# EuroDrum.net
KiCad netlist of a schematic drawn in EAGLE
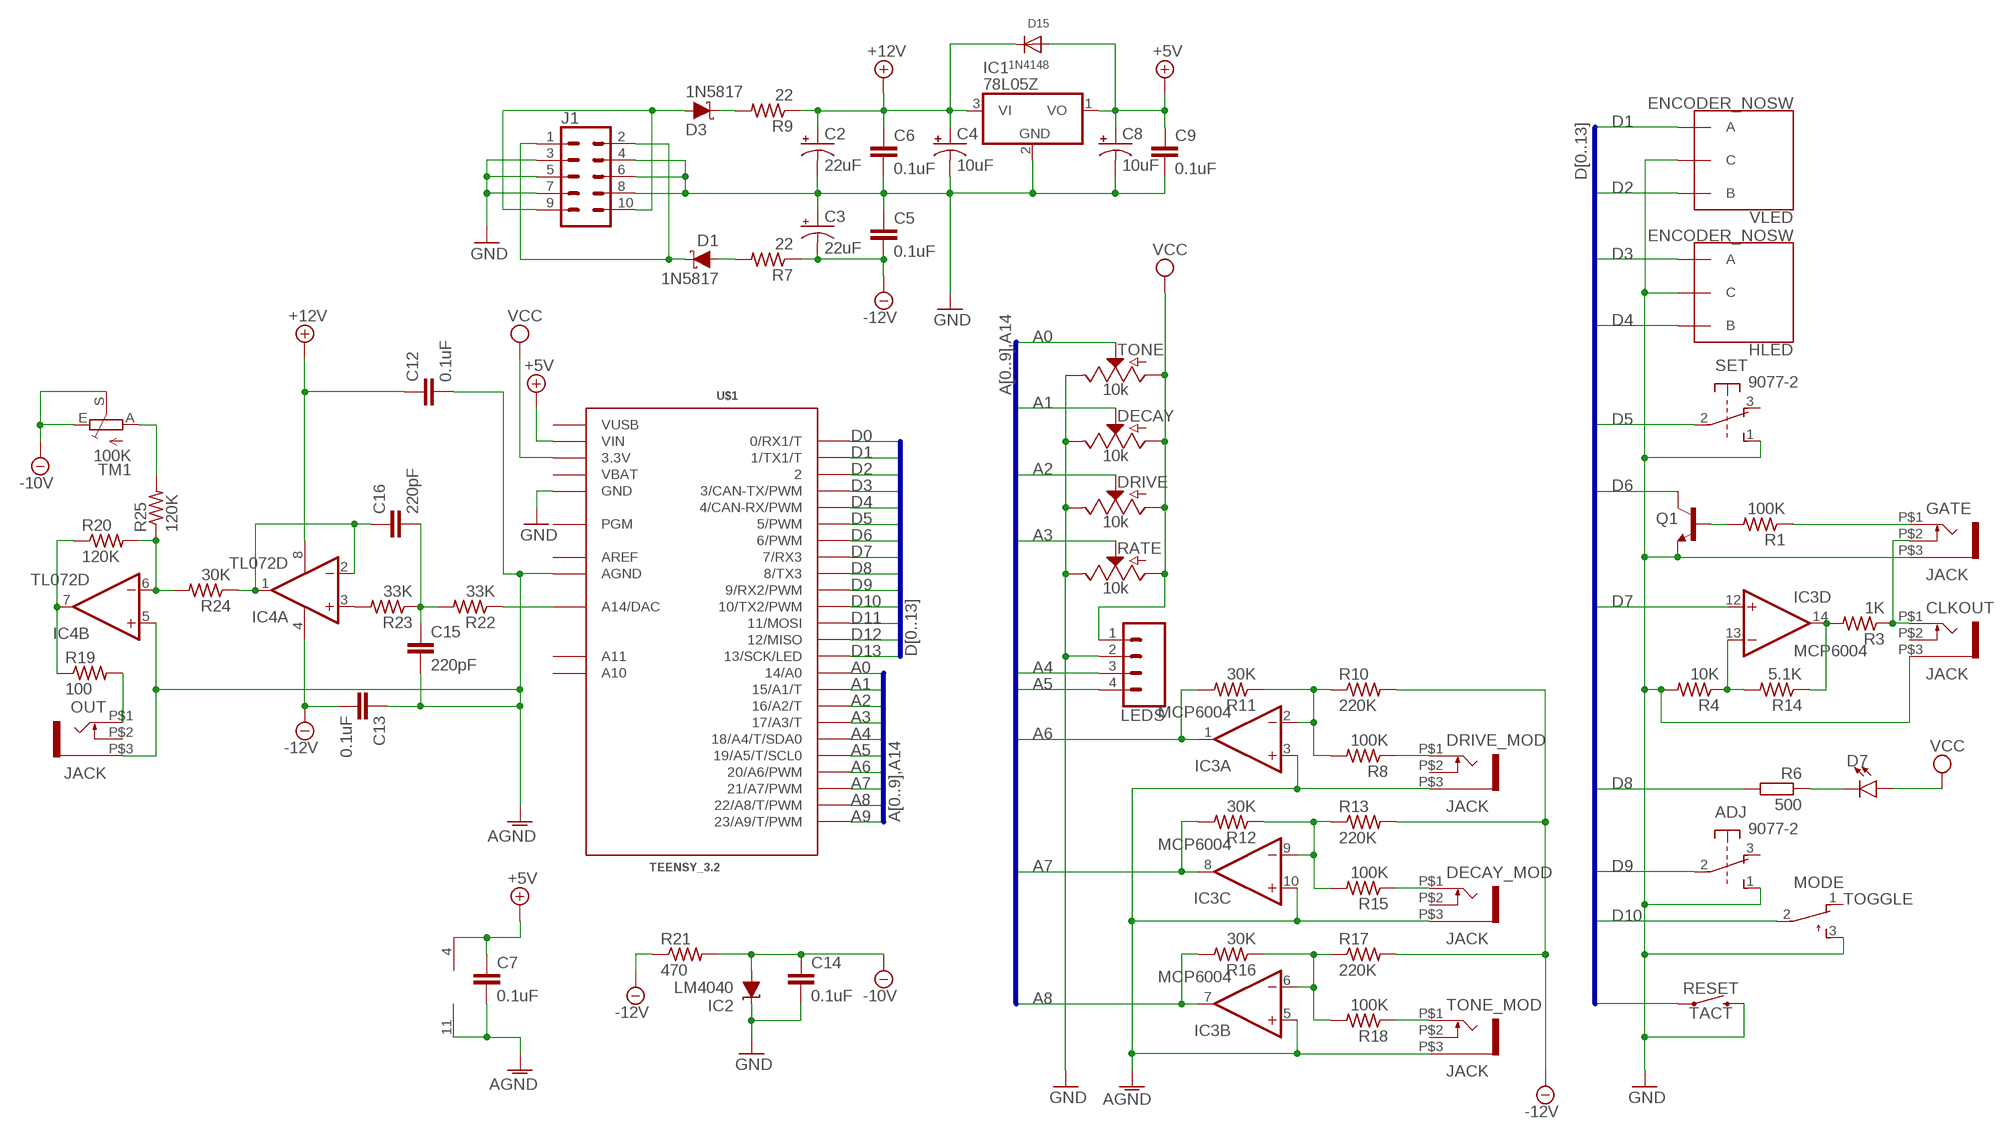
[diagram p0: schematic, sheet 1]

(export (version "E")
  (design (tool "Eeschema 10.0.6"))
  (components
    (comp (ref "ADJ")
      (value "9077-2")
      (footprint "eagle-import:9077-2")
      (libsource (lib "eagle-import") (part "9077-2"))
    )
    (comp (ref "C2")
      (value "22uF")
      (footprint "eagle-import:CPOL-RADIAL-2.5MM-5MM")
      (libsource (lib "eagle-import") (part "10UF-POLAR-RADIAL-2.5MM-25V-20%"))
    )
    (comp (ref "C3")
      (value "22uF")
      (footprint "eagle-import:CPOL-RADIAL-2.5MM-5MM")
      (libsource (lib "eagle-import") (part "10UF-POLAR-RADIAL-2.5MM-25V-20%"))
    )
    (comp (ref "C4")
      (value "10uF")
      (footprint "eagle-import:CPOL-RADIAL-2.5MM-5MM")
      (libsource (lib "eagle-import") (part "10UF-POLAR-RADIAL-2.5MM-25V-20%"))
    )
    (comp (ref "C5")
      (value "0.1uF")
      (footprint "eagle-import:C0603K")
      (libsource (lib "eagle-import") (part "C-EUC0603K"))
    )
    (comp (ref "C6")
      (value "0.1uF")
      (footprint "eagle-import:C0603K")
      (libsource (lib "eagle-import") (part "C-EUC0603K"))
    )
    (comp (ref "C7")
      (value "0.1uF")
      (footprint "eagle-import:C0603K")
      (libsource (lib "eagle-import") (part "C-EUC0603K"))
    )
    (comp (ref "C8")
      (value "10uF")
      (footprint "eagle-import:CPOL-RADIAL-2.5MM-5MM")
      (libsource (lib "eagle-import") (part "10UF-POLAR-RADIAL-2.5MM-25V-20%"))
    )
    (comp (ref "C9")
      (value "0.1uF")
      (footprint "eagle-import:C0603K")
      (libsource (lib "eagle-import") (part "C-EUC0603K"))
    )
    (comp (ref "C12")
      (value "0.1uF")
      (footprint "eagle-import:C0603K")
      (libsource (lib "eagle-import") (part "C-EUC0603K"))
    )
    (comp (ref "C13")
      (value "0.1uF")
      (footprint "eagle-import:C0603K")
      (libsource (lib "eagle-import") (part "C-EUC0603K"))
    )
    (comp (ref "C14")
      (value "0.1uF")
      (footprint "eagle-import:C0603K")
      (libsource (lib "eagle-import") (part "C-EUC0603K"))
    )
    (comp (ref "C15")
      (value "220pF")
      (footprint "eagle-import:C0603K")
      (libsource (lib "eagle-import") (part "C-EUC0603K"))
    )
    (comp (ref "C16")
      (value "220pF")
      (footprint "eagle-import:C0603K")
      (libsource (lib "eagle-import") (part "C-EUC0603K"))
    )
    (comp (ref "CLKOUT")
      (value "JACK")
      (footprint "eagle-import:WQP-PJ301M-12_JACK")
      (libsource (lib "eagle-import") (part "WQP-PJ301M-12_JACK"))
    )
    (comp (ref "D1")
      (value "1N5817")
      (footprint "eagle-import:SOD-323")
      (libsource (lib "eagle-import") (part "DIODE-SCHOTTKY-BAT60A"))
    )
    (comp (ref "D3")
      (value "1N5817")
      (footprint "eagle-import:SOD-323")
      (libsource (lib "eagle-import") (part "DIODE-SCHOTTKY-BAT60A"))
    )
    (comp (ref "D7")
      (value "LED3MM")
      (footprint "eagle-import:LED_3MM")
      (fields (field (name "PROD_ID") "DIO-08794"))
      (libsource (lib "eagle-import") (part "LED3MM"))
    )
    (comp (ref "D15")
      (value "1N4148")
      (footprint "eagle-import:SOD-123")
      (libsource (lib "eagle-import") (part "DIODESOD-123"))
    )
    (comp (ref "DECAY")
      (value "10k")
      (footprint "eagle-import:POT-PTH-ALPS")
      (libsource (lib "eagle-import") (part "POTENTIOMETER-PTH-9MM-1/20W-20%"))
    )
    (comp (ref "DECAY_MOD")
      (value "JACK")
      (footprint "eagle-import:WQP-PJ301M-12_JACK")
      (libsource (lib "eagle-import") (part "WQP-PJ301M-12_JACK"))
    )
    (comp (ref "DRIVE")
      (value "10k")
      (footprint "eagle-import:POT-PTH-ALPS")
      (libsource (lib "eagle-import") (part "POTENTIOMETER-PTH-9MM-1/20W-20%"))
    )
    (comp (ref "DRIVE_MOD")
      (value "JACK")
      (footprint "eagle-import:WQP-PJ301M-12_JACK")
      (libsource (lib "eagle-import") (part "WQP-PJ301M-12_JACK"))
    )
    (comp (ref "GATE")
      (value "JACK")
      (footprint "eagle-import:WQP-PJ301M-12_JACK")
      (libsource (lib "eagle-import") (part "WQP-PJ301M-12_JACK"))
    )
    (comp (ref "HLED")
      (value "ENCODER_NOSW")
      (footprint "eagle-import:ENCODER_NOSW")
      (libsource (lib "eagle-import") (part "ENCODER_NOSW"))
    )
    (comp (ref "IC1")
      (value "78L05Z")
      (footprint "eagle-import:TO92")
      (libsource (lib "eagle-import") (part "78ZL05"))
    )
    (comp (ref "IC2")
      (value "LM4040")
      (footprint "eagle-import:DBZ_R-PDSO-G3")
      (fields (field (name "MPN") "LM4041A12IDBZR"))
      (libsource (lib "eagle-import") (part "LM4041DBZA12"))
    )
    (comp (ref "IC3")
      (value "MCP6004")
      (footprint "eagle-import:SO14")
      (libsource (lib "eagle-import") (part "4AMP_P4+11D"))
    )
    (comp (ref "IC4")
      (value "TL072D")
      (footprint "eagle-import:SO08")
      (libsource (lib "eagle-import") (part "TL072D"))
    )
    (comp (ref "J1")
      (value "CONN_05X2SHD")
      (footprint "eagle-import:2X5-SHROUDED")
      (libsource (lib "eagle-import") (part "CONN_05X2SHD"))
    )
    (comp (ref "LEDS")
      (value "CONN_04LONGPADS")
      (footprint "eagle-import:1X04_LONGPADS")
      (libsource (lib "eagle-import") (part "CONN_04LONGPADS"))
    )
    (comp (ref "MODE")
      (value "TOGGLE")
      (footprint "eagle-import:TL3XYO")
      (libsource (lib "eagle-import") (part "TL32YOSP_BKT"))
    )
    (comp (ref "OUT")
      (value "JACK")
      (footprint "eagle-import:WQP-PJ301M-12_JACK")
      (libsource (lib "eagle-import") (part "WQP-PJ301M-12_JACK"))
    )
    (comp (ref "Q1")
      (value "BC549C")
      (footprint "eagle-import:TO92-EBC")
      (libsource (lib "eagle-import") (part "BC549C"))
    )
    (comp (ref "R1")
      (value "100K")
      (footprint "eagle-import:R0603")
      (libsource (lib "eagle-import") (part "rcl_334_R-US_R0603"))
    )
    (comp (ref "R3")
      (value "1K")
      (footprint "eagle-import:R0603")
      (libsource (lib "eagle-import") (part "rcl_334_R-US_R0603"))
    )
    (comp (ref "R4")
      (value "10K")
      (footprint "eagle-import:R0603")
      (libsource (lib "eagle-import") (part "R-US_R0603"))
    )
    (comp (ref "R6")
      (value "500")
      (footprint "eagle-import:R0603")
      (libsource (lib "eagle-import") (part "R-EU_R0603"))
    )
    (comp (ref "R7")
      (value "22")
      (footprint "eagle-import:R0603")
      (libsource (lib "eagle-import") (part "rcl_334_R-US_R0603"))
    )
    (comp (ref "R8")
      (value "100K")
      (footprint "eagle-import:R0603")
      (libsource (lib "eagle-import") (part "rcl_334_R-US_R0603"))
    )
    (comp (ref "R9")
      (value "22")
      (footprint "eagle-import:R0603")
      (libsource (lib "eagle-import") (part "rcl_334_R-US_R0603"))
    )
    (comp (ref "R10")
      (value "220K")
      (footprint "eagle-import:R0603")
      (libsource (lib "eagle-import") (part "rcl_334_R-US_R0603"))
    )
    (comp (ref "R11")
      (value "30K")
      (footprint "eagle-import:R0603")
      (libsource (lib "eagle-import") (part "rcl_334_R-US_R0603"))
    )
    (comp (ref "R12")
      (value "30K")
      (footprint "eagle-import:R0603")
      (libsource (lib "eagle-import") (part "rcl_334_R-US_R0603"))
    )
    (comp (ref "R13")
      (value "220K")
      (footprint "eagle-import:R0603")
      (libsource (lib "eagle-import") (part "rcl_334_R-US_R0603"))
    )
    (comp (ref "R14")
      (value "5.1K")
      (footprint "eagle-import:R0603")
      (libsource (lib "eagle-import") (part "R-US_R0603"))
    )
    (comp (ref "R15")
      (value "100K")
      (footprint "eagle-import:R0603")
      (libsource (lib "eagle-import") (part "rcl_334_R-US_R0603"))
    )
    (comp (ref "R16")
      (value "30K")
      (footprint "eagle-import:R0603")
      (libsource (lib "eagle-import") (part "rcl_334_R-US_R0603"))
    )
    (comp (ref "R17")
      (value "220K")
      (footprint "eagle-import:R0603")
      (libsource (lib "eagle-import") (part "rcl_334_R-US_R0603"))
    )
    (comp (ref "R18")
      (value "100K")
      (footprint "eagle-import:R0603")
      (libsource (lib "eagle-import") (part "rcl_334_R-US_R0603"))
    )
    (comp (ref "R19")
      (value "100")
      (footprint "eagle-import:R0603")
      (libsource (lib "eagle-import") (part "rcl_334_R-US_R0603"))
    )
    (comp (ref "R20")
      (value "120K")
      (footprint "eagle-import:R0603")
      (libsource (lib "eagle-import") (part "rcl_334_R-US_R0603"))
    )
    (comp (ref "R21")
      (value "470")
      (footprint "eagle-import:R0603")
      (libsource (lib "eagle-import") (part "rcl_334_R-US_R0603"))
    )
    (comp (ref "R22")
      (value "33K")
      (footprint "eagle-import:R0603")
      (libsource (lib "eagle-import") (part "rcl_334_R-US_R0603"))
    )
    (comp (ref "R23")
      (value "33K")
      (footprint "eagle-import:R0603")
      (libsource (lib "eagle-import") (part "rcl_334_R-US_R0603"))
    )
    (comp (ref "R24")
      (value "30K")
      (footprint "eagle-import:R0603")
      (libsource (lib "eagle-import") (part "rcl_334_R-US_R0603"))
    )
    (comp (ref "R25")
      (value "120K")
      (footprint "eagle-import:R0603")
      (libsource (lib "eagle-import") (part "rcl_334_R-US_R0603"))
    )
    (comp (ref "RATE")
      (value "10k")
      (footprint "eagle-import:POT-PTH-ALPS")
      (libsource (lib "eagle-import") (part "POTENTIOMETER-PTH-9MM-1/20W-20%"))
    )
    (comp (ref "RESET")
      (value "TACT")
      (footprint "eagle-import:TACTILE_SWITCH_PTH_6.0MM")
      (libsource (lib "eagle-import") (part "MOMENTARY-SWITCH-SPST-PTH-6.0MM"))
    )
    (comp (ref "SET")
      (value "9077-2")
      (footprint "eagle-import:9077-2")
      (libsource (lib "eagle-import") (part "9077-2"))
    )
    (comp (ref "TM1")
      (value "100K")
      (footprint "eagle-import:CA6H")
      (libsource (lib "eagle-import") (part "TRIM_EU-CA6H"))
    )
    (comp (ref "TONE")
      (value "10k")
      (footprint "eagle-import:POT-PTH-ALPS")
      (libsource (lib "eagle-import") (part "POTENTIOMETER-PTH-9MM-1/20W-20%"))
    )
    (comp (ref "TONE_MOD")
      (value "JACK")
      (footprint "eagle-import:WQP-PJ301M-12_JACK")
      (libsource (lib "eagle-import") (part "WQP-PJ301M-12_JACK"))
    )
    (comp (ref "U$1")
      (value "TEENSY_3.2")
      (footprint "eagle-import:TEENSY_3.0-3.2&LC_ALL_PINS")
      (libsource (lib "eagle-import") (part "TEENSY_3.1-3.2_ALL_PINS"))
    )
    (comp (ref "VLED")
      (value "ENCODER_NOSW")
      (footprint "eagle-import:ENCODER_NOSW")
      (libsource (lib "eagle-import") (part "ENCODER_NOSW"))
    )
  )
  (nets
    (net (code "2") (name "+5V") (class "Default")
      (node (ref "C7") (pin "1") (pinfunction "1_1") (pintype "passive"))
      (node (ref "C8") (pin "1") (pinfunction "+_1") (pintype "passive"))
      (node (ref "C9") (pin "1") (pinfunction "1_1") (pintype "passive"))
      (node (ref "D15") (pin "A") (pinfunction "A_A") (pintype "passive"))
      (node (ref "IC1") (pin "1") (pinfunction "VO_1") (pintype "passive"))
      (node (ref "IC3") (pin "4") (pinfunction "V+_4") (pintype "power_in"))
      (node (ref "U$1") (pin "VIN") (pinfunction "VIN_VIN") (pintype "power_in"))
    )
    (net (code "3") (name "+12V") (class "Default")
      (node (ref "C12") (pin "1") (pinfunction "1_1") (pintype "passive"))
      (node (ref "C2") (pin "1") (pinfunction "+_1") (pintype "passive"))
      (node (ref "C4") (pin "1") (pinfunction "+_1") (pintype "passive"))
      (node (ref "C6") (pin "1") (pinfunction "1_1") (pintype "passive"))
      (node (ref "D15") (pin "C") (pinfunction "C_C") (pintype "passive"))
      (node (ref "IC1") (pin "3") (pinfunction "VI_3") (pintype "input"))
      (node (ref "IC4") (pin "8") (pinfunction "V+_8") (pintype "power_in"))
      (node (ref "R9") (pin "1") (pinfunction "1_1") (pintype "passive"))
    )
    (net (code "4") (name "-10V") (class "Default")
      (node (ref "C14") (pin "1") (pinfunction "1_1") (pintype "passive"))
      (node (ref "IC2") (pin "2") (pinfunction "A_2") (pintype "passive"))
      (node (ref "R21") (pin "2") (pinfunction "2_2") (pintype "passive"))
      (node (ref "TM1") (pin "E") (pinfunction "E_E") (pintype "passive"))
      (node (ref "TM1") (pin "S") (pinfunction "S_S") (pintype "passive"))
    )
    (net (code "5") (name "-12V") (class "Default")
      (node (ref "C13") (pin "2") (pinfunction "2_2") (pintype "passive"))
      (node (ref "C3") (pin "2") (pinfunction "-_2") (pintype "passive"))
      (node (ref "C5") (pin "2") (pinfunction "2_2") (pintype "passive"))
      (node (ref "IC4") (pin "4") (pinfunction "V-_4") (pintype "power_in"))
      (node (ref "R10") (pin "2") (pinfunction "2_2") (pintype "passive"))
      (node (ref "R13") (pin "2") (pinfunction "2_2") (pintype "passive"))
      (node (ref "R17") (pin "2") (pinfunction "2_2") (pintype "passive"))
      (node (ref "R21") (pin "1") (pinfunction "1_1") (pintype "passive"))
      (node (ref "R7") (pin "1") (pinfunction "1_1") (pintype "passive"))
    )
    (net (code "6") (name "/A0") (class "Default")
      (node (ref "TONE") (pin "P$2") (pinfunction "S_P$2") (pintype "passive"))
      (node (ref "U$1") (pin "14/A0") (pinfunction "14/A0_14/A0") (pintype "bidirectional"))
    )
    (net (code "7") (name "/A1") (class "Default")
      (node (ref "DECAY") (pin "P$2") (pinfunction "S_P$2") (pintype "passive"))
      (node (ref "U$1") (pin "15/A1") (pinfunction "15/A1/T_15/A1") (pintype "bidirectional"))
    )
    (net (code "8") (name "/A2") (class "Default")
      (node (ref "DRIVE") (pin "P$2") (pinfunction "S_P$2") (pintype "passive"))
      (node (ref "U$1") (pin "16/A2") (pinfunction "16/A2/T_16/A2") (pintype "bidirectional"))
    )
    (net (code "9") (name "/A3") (class "Default")
      (node (ref "RATE") (pin "P$2") (pinfunction "S_P$2") (pintype "passive"))
      (node (ref "U$1") (pin "17/A3") (pinfunction "17/A3/T_17/A3") (pintype "bidirectional"))
    )
    (net (code "10") (name "/A4") (class "Default")
      (node (ref "LEDS") (pin "3") (pinfunction "3_3") (pintype "passive"))
      (node (ref "U$1") (pin "18/A4") (pinfunction "18/A4/T/SDA0_18/A4") (pintype "bidirectional"))
    )
    (net (code "11") (name "/A5") (class "Default")
      (node (ref "LEDS") (pin "4") (pinfunction "4_4") (pintype "passive"))
      (node (ref "U$1") (pin "19/A5") (pinfunction "19/A5/T/SCL0_19/A5") (pintype "bidirectional"))
    )
    (net (code "12") (name "/A6") (class "Default")
      (node (ref "IC3") (pin "1") (pinfunction "OUT_1") (pintype "output"))
      (node (ref "R11") (pin "2") (pinfunction "2_2") (pintype "passive"))
      (node (ref "U$1") (pin "20/A6") (pinfunction "20/A6/PWM_20/A6") (pintype "bidirectional"))
    )
    (net (code "13") (name "/A7") (class "Default")
      (node (ref "IC3") (pin "8") (pinfunction "OUT_8") (pintype "output"))
      (node (ref "R12") (pin "2") (pinfunction "2_2") (pintype "passive"))
      (node (ref "U$1") (pin "21/A7") (pinfunction "21/A7/PWM_21/A7") (pintype "bidirectional"))
    )
    (net (code "14") (name "/A8") (class "Default")
      (node (ref "IC3") (pin "7") (pinfunction "OUT_7") (pintype "output"))
      (node (ref "R16") (pin "2") (pinfunction "2_2") (pintype "passive"))
      (node (ref "U$1") (pin "22/A8") (pinfunction "22/A8/T/PWM_22/A8") (pintype "bidirectional"))
    )
    (net (code "15") (name "/A9") (class "Default")
      (node (ref "U$1") (pin "23/A9") (pinfunction "23/A9/T/PWM_23/A9") (pintype "bidirectional"))
    )
    (net (code "16") (name "/AREF") (class "Default")
      (node (ref "U$1") (pin "AREF") (pinfunction "AREF_AREF") (pintype "power_in"))
    )
    (net (code "17") (name "/D0") (class "Default")
      (node (ref "U$1") (pin "0") (pinfunction "0/RX1/T_0") (pintype "bidirectional"))
    )
    (net (code "18") (name "/D1") (class "Default")
      (node (ref "U$1") (pin "1") (pinfunction "1/TX1/T_1") (pintype "bidirectional"))
      (node (ref "VLED") (pin "A") (pinfunction "A_A") (pintype "bidirectional"))
    )
    (net (code "19") (name "/D2") (class "Default")
      (node (ref "U$1") (pin "2") (pinfunction "2_2") (pintype "bidirectional"))
      (node (ref "VLED") (pin "B") (pinfunction "B_B") (pintype "bidirectional"))
    )
    (net (code "20") (name "/D3") (class "Default")
      (node (ref "HLED") (pin "A") (pinfunction "A_A") (pintype "bidirectional"))
      (node (ref "U$1") (pin "3") (pinfunction "3/CAN-TX/PWM_3") (pintype "bidirectional"))
    )
    (net (code "21") (name "/D4") (class "Default")
      (node (ref "HLED") (pin "B") (pinfunction "B_B") (pintype "bidirectional"))
      (node (ref "U$1") (pin "4") (pinfunction "4/CAN-RX/PWM_4") (pintype "bidirectional"))
    )
    (net (code "22") (name "/D5") (class "Default")
      (node (ref "SET") (pin "2") (pinfunction "P_2") (pintype "passive"))
      (node (ref "U$1") (pin "5") (pinfunction "5/PWM_5") (pintype "bidirectional"))
    )
    (net (code "23") (name "/D6") (class "Default")
      (node (ref "Q1") (pin "C") (pinfunction "C_C") (pintype "passive"))
      (node (ref "U$1") (pin "6") (pinfunction "6/PWM_6") (pintype "bidirectional"))
    )
    (net (code "24") (name "/D7") (class "Default")
      (node (ref "IC3") (pin "12") (pinfunction "+IN_12") (pintype "input"))
      (node (ref "U$1") (pin "7") (pinfunction "7/RX3_7") (pintype "bidirectional"))
    )
    (net (code "25") (name "/D8") (class "Default")
      (node (ref "R6") (pin "2") (pinfunction "2_2") (pintype "passive"))
      (node (ref "U$1") (pin "8") (pinfunction "8/TX3_8") (pintype "bidirectional"))
    )
    (net (code "26") (name "/D9") (class "Default")
      (node (ref "ADJ") (pin "2") (pinfunction "P_2") (pintype "passive"))
      (node (ref "U$1") (pin "9") (pinfunction "9/RX2/PWM_9") (pintype "bidirectional"))
    )
    (net (code "27") (name "/D10") (class "Default")
      (node (ref "MODE") (pin "2") (pinfunction "P_2") (pintype "passive"))
      (node (ref "U$1") (pin "10") (pinfunction "10/TX2/PWM_10") (pintype "bidirectional"))
    )
    (net (code "28") (name "/D11") (class "Default")
      (node (ref "RESET") (pin "1") (pinfunction "1_1") (pintype "passive"))
      (node (ref "U$1") (pin "11") (pinfunction "11/MOSI_11") (pintype "bidirectional"))
    )
    (net (code "29") (name "/D12") (class "Default")
      (node (ref "U$1") (pin "12") (pinfunction "12/MISO_12") (pintype "bidirectional"))
    )
    (net (code "30") (name "/D13") (class "Default")
      (node (ref "U$1") (pin "13") (pinfunction "13/SCK/LED_13") (pintype "bidirectional"))
    )
    (net (code "32") (name "/VBAT") (class "Default")
      (node (ref "U$1") (pin "VBAT") (pinfunction "VBAT_VBAT") (pintype "power_in"))
    )
    (net (code "33") (name "/VUSB") (class "Default")
      (node (ref "U$1") (pin "VUSB") (pinfunction "VUSB_VUSB") (pintype "power_in"))
    )
    (net (code "35") (name "AGND") (class "Default")
      (node (ref "C12") (pin "2") (pinfunction "2_2") (pintype "passive"))
      (node (ref "C13") (pin "1") (pinfunction "1_1") (pintype "passive"))
      (node (ref "C15") (pin "2") (pinfunction "2_2") (pintype "passive"))
      (node (ref "C7") (pin "2") (pinfunction "2_2") (pintype "passive"))
      (node (ref "DECAY_MOD") (pin "P$3") (pinfunction "1_P$3") (pintype "passive"))
      (node (ref "DRIVE_MOD") (pin "P$3") (pinfunction "1_P$3") (pintype "passive"))
      (node (ref "IC3") (pin "10") (pinfunction "+IN_10") (pintype "input"))
      (node (ref "IC3") (pin "11") (pinfunction "V-_11") (pintype "power_in"))
      (node (ref "IC3") (pin "3") (pinfunction "+IN_3") (pintype "input"))
      (node (ref "IC3") (pin "5") (pinfunction "+IN_5") (pintype "input"))
      (node (ref "IC4") (pin "5") (pinfunction "+IN_5") (pintype "input"))
      (node (ref "OUT") (pin "P$3") (pinfunction "1_P$3") (pintype "passive"))
      (node (ref "TONE_MOD") (pin "P$3") (pinfunction "1_P$3") (pintype "passive"))
      (node (ref "U$1") (pin "AGND") (pinfunction "AGND_AGND") (pintype "power_in"))
    )
    (net (code "36") (name "GND") (class "Default")
      (node (ref "ADJ") (pin "1") (pinfunction "S_1") (pintype "passive"))
      (node (ref "C14") (pin "2") (pinfunction "2_2") (pintype "passive"))
      (node (ref "C2") (pin "2") (pinfunction "-_2") (pintype "passive"))
      (node (ref "C3") (pin "1") (pinfunction "+_1") (pintype "passive"))
      (node (ref "C4") (pin "2") (pinfunction "-_2") (pintype "passive"))
      (node (ref "C5") (pin "1") (pinfunction "1_1") (pintype "passive"))
      (node (ref "C6") (pin "2") (pinfunction "2_2") (pintype "passive"))
      (node (ref "C8") (pin "2") (pinfunction "-_2") (pintype "passive"))
      (node (ref "C9") (pin "2") (pinfunction "2_2") (pintype "passive"))
      (node (ref "CLKOUT") (pin "P$3") (pinfunction "1_P$3") (pintype "passive"))
      (node (ref "DECAY") (pin "P$1") (pinfunction "E_P$1") (pintype "passive"))
      (node (ref "DRIVE") (pin "P$1") (pinfunction "E_P$1") (pintype "passive"))
      (node (ref "GATE") (pin "P$3") (pinfunction "1_P$3") (pintype "passive"))
      (node (ref "HLED") (pin "C") (pinfunction "C_C") (pintype "bidirectional"))
      (node (ref "IC1") (pin "2") (pinfunction "GND_2") (pintype "passive"))
      (node (ref "IC2") (pin "1") (pinfunction "C_1") (pintype "passive"))
      (node (ref "J1") (pin "3") (pinfunction "3_3") (pintype "passive"))
      (node (ref "J1") (pin "4") (pinfunction "4_4") (pintype "passive"))
      (node (ref "J1") (pin "5") (pinfunction "5_5") (pintype "passive"))
      (node (ref "J1") (pin "6") (pinfunction "6_6") (pintype "passive"))
      (node (ref "J1") (pin "7") (pinfunction "7_7") (pintype "passive"))
      (node (ref "J1") (pin "8") (pinfunction "8_8") (pintype "passive"))
      (node (ref "LEDS") (pin "2") (pinfunction "2_2") (pintype "passive"))
      (node (ref "MODE") (pin "3") (pinfunction "S_3") (pintype "passive"))
      (node (ref "Q1") (pin "E") (pinfunction "E_E") (pintype "passive"))
      (node (ref "R4") (pin "2") (pinfunction "2_2") (pintype "passive"))
      (node (ref "RATE") (pin "P$1") (pinfunction "E_P$1") (pintype "passive"))
      (node (ref "RESET") (pin "3") (pinfunction "2_3") (pintype "passive"))
      (node (ref "SET") (pin "1") (pinfunction "S_1") (pintype "passive"))
      (node (ref "TONE") (pin "P$1") (pinfunction "E_P$1") (pintype "passive"))
      (node (ref "U$1") (pin "GND") (pinfunction "GND_GND") (pintype "power_in"))
      (node (ref "U$1") (pin "GND1") (pinfunction "GND_GND1") (pintype "power_in"))
      (node (ref "VLED") (pin "C") (pinfunction "C_C") (pintype "bidirectional"))
    )
    (net (code "37") (name "Net-(C15-Pad1)") (class "Default")
      (node (ref "C15") (pin "1") (pinfunction "1_1") (pintype "passive"))
      (node (ref "C16") (pin "2") (pinfunction "2_2") (pintype "passive"))
      (node (ref "R22") (pin "2") (pinfunction "2_2") (pintype "passive"))
      (node (ref "R23") (pin "1") (pinfunction "1_1") (pintype "passive"))
    )
    (net (code "38") (name "Net-(CLKOUT-2)") (class "Default")
      (node (ref "CLKOUT") (pin "P$1") (pinfunction "2_P$1") (pintype "passive"))
      (node (ref "GATE") (pin "P$2") (pinfunction "3_P$2") (pintype "passive"))
      (node (ref "R3") (pin "1") (pinfunction "1_1") (pintype "passive"))
    )
    (net (code "39") (name "Net-(D1-PadA)") (class "Default")
      (node (ref "D1") (pin "A") (pinfunction "A_A") (pintype "passive"))
      (node (ref "R7") (pin "2") (pinfunction "2_2") (pintype "passive"))
    )
    (net (code "40") (name "Net-(D1-PadC)") (class "Default")
      (node (ref "D1") (pin "C") (pinfunction "C_C") (pintype "passive"))
      (node (ref "J1") (pin "1") (pinfunction "1_1") (pintype "passive"))
      (node (ref "J1") (pin "2") (pinfunction "2_2") (pintype "passive"))
    )
    (net (code "41") (name "Net-(D3-PadA)") (class "Default")
      (node (ref "D3") (pin "A") (pinfunction "A_A") (pintype "passive"))
      (node (ref "J1") (pin "10") (pinfunction "10_10") (pintype "passive"))
      (node (ref "J1") (pin "9") (pinfunction "9_9") (pintype "passive"))
    )
    (net (code "42") (name "Net-(D3-PadC)") (class "Default")
      (node (ref "D3") (pin "C") (pinfunction "C_C") (pintype "passive"))
      (node (ref "R9") (pin "2") (pinfunction "2_2") (pintype "passive"))
    )
    (net (code "43") (name "Net-(D7-C)") (class "Default")
      (node (ref "D7") (pin "K") (pinfunction "C_K") (pintype "passive"))
      (node (ref "R6") (pin "1") (pinfunction "1_1") (pintype "passive"))
    )
    (net (code "44") (name "Net-(DECAY_MOD-2)") (class "Default")
      (node (ref "DECAY_MOD") (pin "P$1") (pinfunction "2_P$1") (pintype "passive"))
      (node (ref "R15") (pin "1") (pinfunction "1_1") (pintype "passive"))
    )
    (net (code "45") (name "Net-(DRIVE_MOD-2)") (class "Default")
      (node (ref "DRIVE_MOD") (pin "P$1") (pinfunction "2_P$1") (pintype "passive"))
      (node (ref "R8") (pin "1") (pinfunction "1_1") (pintype "passive"))
    )
    (net (code "46") (name "Net-(GATE-2)") (class "Default")
      (node (ref "GATE") (pin "P$1") (pinfunction "2_P$1") (pintype "passive"))
      (node (ref "R1") (pin "1") (pinfunction "1_1") (pintype "passive"))
    )
    (net (code "47") (name "Net-(IC3A--IN)") (class "Default")
      (node (ref "IC3") (pin "2") (pinfunction "-IN_2") (pintype "input"))
      (node (ref "R10") (pin "1") (pinfunction "1_1") (pintype "passive"))
      (node (ref "R11") (pin "1") (pinfunction "1_1") (pintype "passive"))
      (node (ref "R8") (pin "2") (pinfunction "2_2") (pintype "passive"))
    )
    (net (code "48") (name "Net-(IC3B--IN)") (class "Default")
      (node (ref "IC3") (pin "6") (pinfunction "-IN_6") (pintype "input"))
      (node (ref "R16") (pin "1") (pinfunction "1_1") (pintype "passive"))
      (node (ref "R17") (pin "1") (pinfunction "1_1") (pintype "passive"))
      (node (ref "R18") (pin "2") (pinfunction "2_2") (pintype "passive"))
    )
    (net (code "49") (name "Net-(IC3C--IN)") (class "Default")
      (node (ref "IC3") (pin "9") (pinfunction "-IN_9") (pintype "input"))
      (node (ref "R12") (pin "1") (pinfunction "1_1") (pintype "passive"))
      (node (ref "R13") (pin "1") (pinfunction "1_1") (pintype "passive"))
      (node (ref "R15") (pin "2") (pinfunction "2_2") (pintype "passive"))
    )
    (net (code "50") (name "Net-(IC3D--IN)") (class "Default")
      (node (ref "IC3") (pin "13") (pinfunction "-IN_13") (pintype "input"))
      (node (ref "R14") (pin "2") (pinfunction "2_2") (pintype "passive"))
      (node (ref "R4") (pin "1") (pinfunction "1_1") (pintype "passive"))
    )
    (net (code "51") (name "Net-(IC3D-OUT)") (class "Default")
      (node (ref "IC3") (pin "14") (pinfunction "OUT_14") (pintype "output"))
      (node (ref "R14") (pin "1") (pinfunction "1_1") (pintype "passive"))
      (node (ref "R3") (pin "2") (pinfunction "2_2") (pintype "passive"))
    )
    (net (code "52") (name "Net-(IC4A-+IN)") (class "Default")
      (node (ref "IC4") (pin "3") (pinfunction "+IN_3") (pintype "input"))
      (node (ref "R23") (pin "2") (pinfunction "2_2") (pintype "passive"))
    )
    (net (code "53") (name "Net-(IC4A--IN)") (class "Default")
      (node (ref "C16") (pin "1") (pinfunction "1_1") (pintype "passive"))
      (node (ref "IC4") (pin "1") (pinfunction "OUT_1") (pintype "output"))
      (node (ref "IC4") (pin "2") (pinfunction "-IN_2") (pintype "input"))
      (node (ref "R24") (pin "1") (pinfunction "1_1") (pintype "passive"))
    )
    (net (code "54") (name "Net-(IC4B--IN)") (class "Default")
      (node (ref "IC4") (pin "6") (pinfunction "-IN_6") (pintype "input"))
      (node (ref "R20") (pin "2") (pinfunction "2_2") (pintype "passive"))
      (node (ref "R24") (pin "2") (pinfunction "2_2") (pintype "passive"))
      (node (ref "R25") (pin "1") (pinfunction "1_1") (pintype "passive"))
    )
    (net (code "55") (name "Net-(IC4B-OUT)") (class "Default")
      (node (ref "IC4") (pin "7") (pinfunction "OUT_7") (pintype "output"))
      (node (ref "R19") (pin "1") (pinfunction "1_1") (pintype "passive"))
      (node (ref "R20") (pin "1") (pinfunction "1_1") (pintype "passive"))
    )
    (net (code "56") (name "Net-(OUT-2)") (class "Default")
      (node (ref "OUT") (pin "P$1") (pinfunction "2_P$1") (pintype "passive"))
      (node (ref "R19") (pin "2") (pinfunction "2_2") (pintype "passive"))
    )
    (net (code "57") (name "Net-(Q1-PadB)") (class "Default")
      (node (ref "Q1") (pin "B") (pinfunction "B_B") (pintype "passive"))
      (node (ref "R1") (pin "2") (pinfunction "2_2") (pintype "passive"))
    )
    (net (code "58") (name "Net-(R25-Pad2)") (class "Default")
      (node (ref "R25") (pin "2") (pinfunction "2_2") (pintype "passive"))
      (node (ref "TM1") (pin "A") (pinfunction "A_A") (pintype "passive"))
    )
    (net (code "59") (name "Net-(TONE_MOD-2)") (class "Default")
      (node (ref "R18") (pin "1") (pinfunction "1_1") (pintype "passive"))
      (node (ref "TONE_MOD") (pin "P$1") (pinfunction "2_P$1") (pintype "passive"))
    )
    (net (code "60") (name "Net-(U$1-A14{slash}DAC)") (class "Default")
      (node (ref "R22") (pin "1") (pinfunction "1_1") (pintype "passive"))
      (node (ref "U$1") (pin "RESET/DAC") (pinfunction "A14/DAC_RESET/DAC") (pintype "bidirectional"))
    )
    (net (code "61") (name "VCC") (class "Default")
      (node (ref "D7") (pin "A") (pinfunction "A_A") (pintype "passive"))
      (node (ref "DECAY") (pin "P$3") (pinfunction "A_P$3") (pintype "passive"))
      (node (ref "DRIVE") (pin "P$3") (pinfunction "A_P$3") (pintype "passive"))
      (node (ref "LEDS") (pin "1") (pinfunction "1_1") (pintype "passive"))
      (node (ref "RATE") (pin "P$3") (pinfunction "A_P$3") (pintype "passive"))
      (node (ref "TONE") (pin "P$3") (pinfunction "A_P$3") (pintype "passive"))
      (node (ref "U$1") (pin "3.3V") (pinfunction "3.3V_3.3V") (pintype "power_in"))
      (node (ref "U$1") (pin "3.3V1") (pinfunction "3.3V_3.3V1") (pintype "power_in"))
    )
    (net (code "62") (name "unconnected-(ADJA-O-Pad3)") (class "Default")
      (node (ref "ADJ") (pin "3") (pinfunction "O_3") (pintype "passive"))
    )
    (net (code "63") (name "unconnected-(CLKOUT-3-PadP$2)") (class "Default")
      (node (ref "CLKOUT") (pin "P$2") (pinfunction "3_P$2") (pintype "passive"))
    )
    (net (code "64") (name "unconnected-(DECAY_MOD-3-PadP$2)") (class "Default")
      (node (ref "DECAY_MOD") (pin "P$2") (pinfunction "3_P$2") (pintype "passive"))
    )
    (net (code "65") (name "unconnected-(DRIVE_MOD-3-PadP$2)") (class "Default")
      (node (ref "DRIVE_MOD") (pin "P$2") (pinfunction "3_P$2") (pintype "passive"))
    )
    (net (code "66") (name "unconnected-(MODE-O-Pad1)") (class "Default")
      (node (ref "MODE") (pin "1") (pinfunction "O_1") (pintype "passive"))
    )
    (net (code "67") (name "unconnected-(OUT-3-PadP$2)") (class "Default")
      (node (ref "OUT") (pin "P$2") (pinfunction "3_P$2") (pintype "passive"))
    )
    (net (code "68") (name "unconnected-(SETA-O-Pad3)") (class "Default")
      (node (ref "SET") (pin "3") (pinfunction "O_3") (pintype "passive"))
    )
    (net (code "69") (name "unconnected-(TONE_MOD-3-PadP$2)") (class "Default")
      (node (ref "TONE_MOD") (pin "P$2") (pinfunction "3_P$2") (pintype "passive"))
    )
    (net (code "70") (name "unconnected-(U$1-PadA10)") (class "Default")
      (node (ref "U$1") (pin "A10") (pinfunction "A10_A10") (pintype "bidirectional"))
    )
    (net (code "71") (name "unconnected-(U$1-PadA11)") (class "Default")
      (node (ref "U$1") (pin "A11") (pinfunction "A11_A11") (pintype "bidirectional"))
    )
    (net (code "72") (name "unconnected-(U$1-PadPGM)") (class "Default")
      (node (ref "U$1") (pin "PGM") (pinfunction "PGM_PGM") (pintype "bidirectional"))
    )
  )
)
